# LoRa_Concentrator.net
KiCad netlist of a schematic drawn in Altium Designer
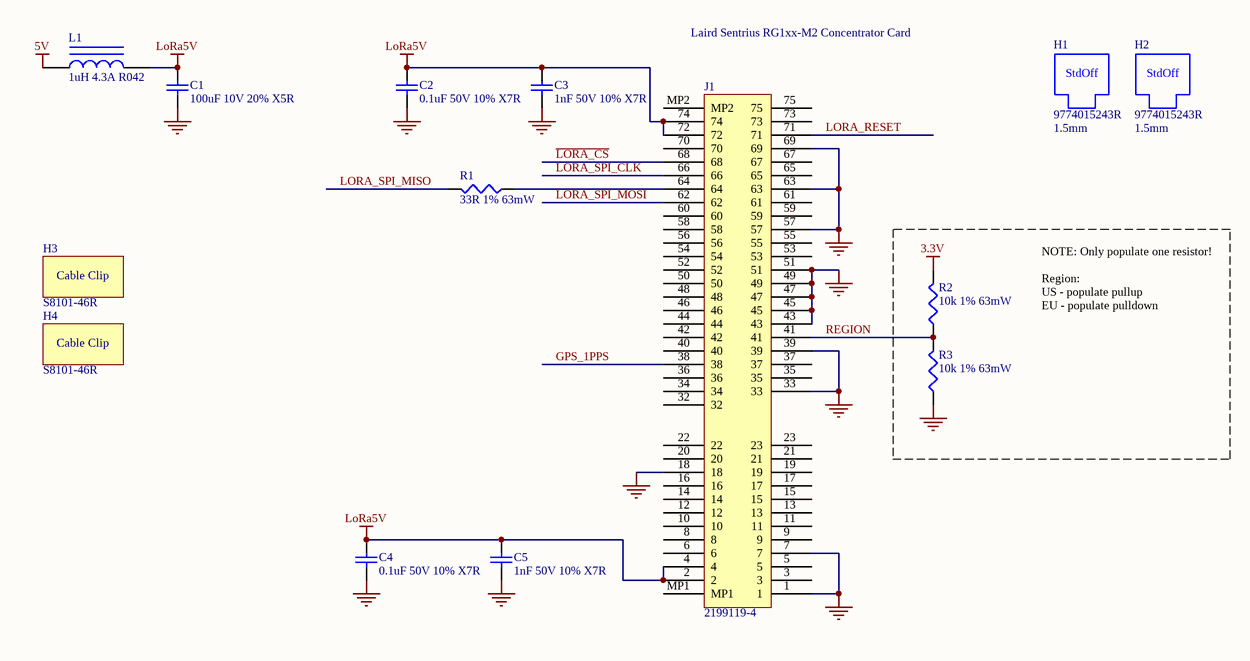
[diagram p0: LoRa Concentrator.SchDoc]

(export (version "E")
  (design (tool "Eeschema 10.0.6"))
  (components
    (comp (ref "C1")
      (value "100uF 10V 20% X5R")
      (footprint "C1210_L")
      (description "Capacitor")
      (libsource (lib "Miscellaneous Devices") (part "Cap"))
    )
    (comp (ref "C2")
      (value "0.1uF 50V 10% X7R")
      (footprint "CAPC1005L")
      (description "Capacitor")
      (libsource (lib "Miscellaneous Devices") (part "Cap"))
    )
    (comp (ref "C3")
      (value "1nF 50V 10% X7R")
      (footprint "CAPC1005L")
      (description "Capacitor")
      (libsource (lib "Miscellaneous Devices") (part "Cap"))
    )
    (comp (ref "C4")
      (value "0.1uF 50V 10% X7R")
      (footprint "CAPC1005L")
      (description "Capacitor")
      (libsource (lib "Miscellaneous Devices") (part "Cap"))
    )
    (comp (ref "C5")
      (value "1nF 50V 10% X7R")
      (footprint "CAPC1005L")
      (description "Capacitor")
      (libsource (lib "Miscellaneous Devices") (part "Cap"))
    )
    (comp (ref "H1")
      (value "9774015243R")
      (footprint "Wurth 9774015243R")
      (description "RND STANDOFF M2X0.4 STEEL")
      (fields (field (name "MANUFACTURER") "Wurth Electronics Inc") (field (name "HEIGHT") "1.5mm"))
      (libsource (lib "Latium Component Library") (part "SMD 1.5mm Spacer"))
    )
    (comp (ref "H2")
      (value "9774015243R")
      (footprint "Wurth 9774015243R")
      (description "RND STANDOFF M2X0.4 STEEL")
      (fields (field (name "MANUFACTURER") "Wurth Electronics Inc") (field (name "HEIGHT") "1.5mm"))
      (libsource (lib "Latium Component Library") (part "SMD 1.5mm Spacer"))
    )
    (comp (ref "H3")
      (value "S8101-46R")
      (footprint "Coax Cable Clip")
      (description "CBL CLIP C-TYPE SILVER SOLDER")
      (fields (field (name "MANUFACTURER") "Harwin Inc"))
      (libsource (lib "Latium Component Library") (part "Cable Clip"))
    )
    (comp (ref "H4")
      (value "S8101-46R")
      (footprint "Coax Cable Clip")
      (description "CBL CLIP C-TYPE SILVER SOLDER")
      (fields (field (name "MANUFACTURER") "Harwin Inc"))
      (libsource (lib "Latium Component Library") (part "Cable Clip"))
    )
    (comp (ref "J1")
      (value "2199119-4")
      (footprint "TE 2199119-4")
      (description "CONN FEMALE 67POS 0.020 GOLD")
      (fields (field (name "MANUFACTURER") "TE Connectivity AMP Connectors"))
      (libsource (lib "Latium Component Library") (part "TE2199119-4"))
    )
    (comp (ref "L1")
      (value "1uH 4.3A R042")
      (footprint "WE-LQS 252012")
      (description "FIXED IND 1UH 4.3A 42 MOHM SMD")
      (fields
        (field (name "MANUFACTURER PART NUMBER") "DFE252012P-1R0M=P2")
        (field (name "MANUFACTURER") "Murata Electronics")
      )
      (libsource (lib "Miscellaneous Devices") (part "Inductor Iron"))
    )
    (comp (ref "R1")
      (value "33R 1% 63mW")
      (footprint "RESC1005L")
      (description "Resistor")
      (libsource (lib "Miscellaneous Devices") (part "Res3"))
    )
    (comp (ref "R2")
      (value "10k 1% 63mW")
      (footprint "RESC1005L")
      (description "Resistor")
      (libsource (lib "Miscellaneous Devices") (part "Res3"))
    )
    (comp (ref "R3")
      (value "10k 1% 63mW")
      (footprint "RESC1005L")
      (description "Resistor")
      (libsource (lib "Miscellaneous Devices") (part "Res3"))
    )
  )
  (nets
    (net (code "1") (name "/GPS_1PPS") (class "Default")
      (node (ref "J1") (pin "38") (pinfunction "38_38") (pintype "passive"))
    )
    (net (code "2") (name "/LORA_RESET") (class "Default")
      (node (ref "J1") (pin "71") (pinfunction "71_71") (pintype "passive"))
    )
    (net (code "3") (name "/LORA_SPI_CLK") (class "Default")
      (node (ref "J1") (pin "66") (pinfunction "66_66") (pintype "passive"))
    )
    (net (code "4") (name "/LORA_SPI_MISO") (class "Default")
      (node (ref "R1") (pin "2") (pinfunction "2_2") (pintype "passive"))
    )
    (net (code "5") (name "/LORA_SPI_MOSI") (class "Default")
      (node (ref "J1") (pin "62") (pinfunction "62_62") (pintype "passive"))
    )
    (net (code "6") (name "/REGION") (class "Default")
      (node (ref "J1") (pin "41") (pinfunction "41_41") (pintype "passive"))
      (node (ref "R2") (pin "1") (pinfunction "1_1") (pintype "passive"))
      (node (ref "R3") (pin "2") (pinfunction "2_2") (pintype "passive"))
    )
    (net (code "7") (name "/~{LORA_CS}") (class "Default")
      (node (ref "J1") (pin "68") (pinfunction "68_68") (pintype "passive"))
    )
    (net (code "8") (name "3.3V") (class "Default")
      (node (ref "R2") (pin "2") (pinfunction "2_2") (pintype "passive"))
    )
    (net (code "9") (name "5V") (class "Default")
      (node (ref "L1") (pin "1") (pinfunction "1_1") (pintype "passive"))
    )
    (net (code "10") (name "GND") (class "Default")
      (node (ref "C1") (pin "1") (pinfunction "1_1") (pintype "passive"))
      (node (ref "C2") (pin "2") (pinfunction "2_2") (pintype "passive"))
      (node (ref "C3") (pin "2") (pinfunction "2_2") (pintype "passive"))
      (node (ref "C4") (pin "2") (pinfunction "2_2") (pintype "passive"))
      (node (ref "C5") (pin "2") (pinfunction "2_2") (pintype "passive"))
      (node (ref "J1") (pin "1") (pinfunction "1_1") (pintype "passive"))
      (node (ref "J1") (pin "18") (pinfunction "18_18") (pintype "passive"))
      (node (ref "J1") (pin "33") (pinfunction "33_33") (pintype "passive"))
      (node (ref "J1") (pin "39") (pinfunction "39_39") (pintype "passive"))
      (node (ref "J1") (pin "43") (pinfunction "43_43") (pintype "passive"))
      (node (ref "J1") (pin "45") (pinfunction "45_45") (pintype "passive"))
      (node (ref "J1") (pin "47") (pinfunction "47_47") (pintype "passive"))
      (node (ref "J1") (pin "49") (pinfunction "49_49") (pintype "passive"))
      (node (ref "J1") (pin "51") (pinfunction "51_51") (pintype "passive"))
      (node (ref "J1") (pin "57") (pinfunction "57_57") (pintype "passive"))
      (node (ref "J1") (pin "63") (pinfunction "63_63") (pintype "passive"))
      (node (ref "J1") (pin "69") (pinfunction "69_69") (pintype "passive"))
      (node (ref "J1") (pin "7") (pinfunction "7_7") (pintype "passive"))
      (node (ref "R3") (pin "1") (pinfunction "1_1") (pintype "passive"))
    )
    (net (code "11") (name "LoRa5V") (class "Default")
      (node (ref "C1") (pin "2") (pinfunction "2_2") (pintype "passive"))
      (node (ref "C2") (pin "1") (pinfunction "1_1") (pintype "passive"))
      (node (ref "C3") (pin "1") (pinfunction "1_1") (pintype "passive"))
      (node (ref "C4") (pin "1") (pinfunction "1_1") (pintype "passive"))
      (node (ref "C5") (pin "1") (pinfunction "1_1") (pintype "passive"))
      (node (ref "J1") (pin "2") (pinfunction "2_2") (pintype "passive"))
      (node (ref "J1") (pin "4") (pinfunction "4_4") (pintype "passive"))
      (node (ref "J1") (pin "72") (pinfunction "72_72") (pintype "passive"))
      (node (ref "J1") (pin "74") (pinfunction "74_74") (pintype "passive"))
      (node (ref "L1") (pin "2") (pinfunction "2_2") (pintype "passive"))
    )
    (net (code "12") (name "Net-(J1-Pad64)") (class "Default")
      (node (ref "J1") (pin "64") (pinfunction "64_64") (pintype "passive"))
      (node (ref "R1") (pin "1") (pinfunction "1_1") (pintype "passive"))
    )
    (net (code "13") (name "unconnected-(J1-Pad3)") (class "Default")
      (node (ref "J1") (pin "3") (pinfunction "3_3") (pintype "passive"))
    )
    (net (code "14") (name "unconnected-(J1-Pad5)") (class "Default")
      (node (ref "J1") (pin "5") (pinfunction "5_5") (pintype "passive"))
    )
    (net (code "15") (name "unconnected-(J1-Pad6)") (class "Default")
      (node (ref "J1") (pin "6") (pinfunction "6_6") (pintype "passive"))
    )
    (net (code "16") (name "unconnected-(J1-Pad8)") (class "Default")
      (node (ref "J1") (pin "8") (pinfunction "8_8") (pintype "passive"))
    )
    (net (code "17") (name "unconnected-(J1-Pad9)") (class "Default")
      (node (ref "J1") (pin "9") (pinfunction "9_9") (pintype "passive"))
    )
    (net (code "18") (name "unconnected-(J1-Pad10)") (class "Default")
      (node (ref "J1") (pin "10") (pinfunction "10_10") (pintype "passive"))
    )
    (net (code "19") (name "unconnected-(J1-Pad11)") (class "Default")
      (node (ref "J1") (pin "11") (pinfunction "11_11") (pintype "passive"))
    )
    (net (code "20") (name "unconnected-(J1-Pad12)") (class "Default")
      (node (ref "J1") (pin "12") (pinfunction "12_12") (pintype "passive"))
    )
    (net (code "21") (name "unconnected-(J1-Pad13)") (class "Default")
      (node (ref "J1") (pin "13") (pinfunction "13_13") (pintype "passive"))
    )
    (net (code "22") (name "unconnected-(J1-Pad14)") (class "Default")
      (node (ref "J1") (pin "14") (pinfunction "14_14") (pintype "passive"))
    )
    (net (code "23") (name "unconnected-(J1-Pad15)") (class "Default")
      (node (ref "J1") (pin "15") (pinfunction "15_15") (pintype "passive"))
    )
    (net (code "24") (name "unconnected-(J1-Pad16)") (class "Default")
      (node (ref "J1") (pin "16") (pinfunction "16_16") (pintype "passive"))
    )
    (net (code "25") (name "unconnected-(J1-Pad17)") (class "Default")
      (node (ref "J1") (pin "17") (pinfunction "17_17") (pintype "passive"))
    )
    (net (code "26") (name "unconnected-(J1-Pad19)") (class "Default")
      (node (ref "J1") (pin "19") (pinfunction "19_19") (pintype "passive"))
    )
    (net (code "27") (name "unconnected-(J1-Pad20)") (class "Default")
      (node (ref "J1") (pin "20") (pinfunction "20_20") (pintype "passive"))
    )
    (net (code "28") (name "unconnected-(J1-Pad21)") (class "Default")
      (node (ref "J1") (pin "21") (pinfunction "21_21") (pintype "passive"))
    )
    (net (code "29") (name "unconnected-(J1-Pad22)") (class "Default")
      (node (ref "J1") (pin "22") (pinfunction "22_22") (pintype "passive"))
    )
    (net (code "30") (name "unconnected-(J1-Pad23)") (class "Default")
      (node (ref "J1") (pin "23") (pinfunction "23_23") (pintype "passive"))
    )
    (net (code "31") (name "unconnected-(J1-Pad32)") (class "Default")
      (node (ref "J1") (pin "32") (pinfunction "32_32") (pintype "passive"))
    )
    (net (code "32") (name "unconnected-(J1-Pad34)") (class "Default")
      (node (ref "J1") (pin "34") (pinfunction "34_34") (pintype "passive"))
    )
    (net (code "33") (name "unconnected-(J1-Pad35)") (class "Default")
      (node (ref "J1") (pin "35") (pinfunction "35_35") (pintype "passive"))
    )
    (net (code "34") (name "unconnected-(J1-Pad36)") (class "Default")
      (node (ref "J1") (pin "36") (pinfunction "36_36") (pintype "passive"))
    )
    (net (code "35") (name "unconnected-(J1-Pad37)") (class "Default")
      (node (ref "J1") (pin "37") (pinfunction "37_37") (pintype "passive"))
    )
    (net (code "36") (name "unconnected-(J1-Pad40)") (class "Default")
      (node (ref "J1") (pin "40") (pinfunction "40_40") (pintype "passive"))
    )
    (net (code "37") (name "unconnected-(J1-Pad42)") (class "Default")
      (node (ref "J1") (pin "42") (pinfunction "42_42") (pintype "passive"))
    )
    (net (code "38") (name "unconnected-(J1-Pad44)") (class "Default")
      (node (ref "J1") (pin "44") (pinfunction "44_44") (pintype "passive"))
    )
    (net (code "39") (name "unconnected-(J1-Pad46)") (class "Default")
      (node (ref "J1") (pin "46") (pinfunction "46_46") (pintype "passive"))
    )
    (net (code "40") (name "unconnected-(J1-Pad48)") (class "Default")
      (node (ref "J1") (pin "48") (pinfunction "48_48") (pintype "passive"))
    )
    (net (code "41") (name "unconnected-(J1-Pad50)") (class "Default")
      (node (ref "J1") (pin "50") (pinfunction "50_50") (pintype "passive"))
    )
    (net (code "42") (name "unconnected-(J1-Pad52)") (class "Default")
      (node (ref "J1") (pin "52") (pinfunction "52_52") (pintype "passive"))
    )
    (net (code "43") (name "unconnected-(J1-Pad53)") (class "Default")
      (node (ref "J1") (pin "53") (pinfunction "53_53") (pintype "passive"))
    )
    (net (code "44") (name "unconnected-(J1-Pad54)") (class "Default")
      (node (ref "J1") (pin "54") (pinfunction "54_54") (pintype "passive"))
    )
    (net (code "45") (name "unconnected-(J1-Pad55)") (class "Default")
      (node (ref "J1") (pin "55") (pinfunction "55_55") (pintype "passive"))
    )
    (net (code "46") (name "unconnected-(J1-Pad56)") (class "Default")
      (node (ref "J1") (pin "56") (pinfunction "56_56") (pintype "passive"))
    )
    (net (code "47") (name "unconnected-(J1-Pad58)") (class "Default")
      (node (ref "J1") (pin "58") (pinfunction "58_58") (pintype "passive"))
    )
    (net (code "48") (name "unconnected-(J1-Pad59)") (class "Default")
      (node (ref "J1") (pin "59") (pinfunction "59_59") (pintype "passive"))
    )
    (net (code "49") (name "unconnected-(J1-Pad60)") (class "Default")
      (node (ref "J1") (pin "60") (pinfunction "60_60") (pintype "passive"))
    )
    (net (code "50") (name "unconnected-(J1-Pad61)") (class "Default")
      (node (ref "J1") (pin "61") (pinfunction "61_61") (pintype "passive"))
    )
    (net (code "51") (name "unconnected-(J1-Pad65)") (class "Default")
      (node (ref "J1") (pin "65") (pinfunction "65_65") (pintype "passive"))
    )
    (net (code "52") (name "unconnected-(J1-Pad67)") (class "Default")
      (node (ref "J1") (pin "67") (pinfunction "67_67") (pintype "passive"))
    )
    (net (code "53") (name "unconnected-(J1-Pad70)") (class "Default")
      (node (ref "J1") (pin "70") (pinfunction "70_70") (pintype "passive"))
    )
    (net (code "54") (name "unconnected-(J1-Pad73)") (class "Default")
      (node (ref "J1") (pin "73") (pinfunction "73_73") (pintype "passive"))
    )
    (net (code "55") (name "unconnected-(J1-Pad75)") (class "Default")
      (node (ref "J1") (pin "75") (pinfunction "75_75") (pintype "passive"))
    )
    (net (code "56") (name "unconnected-(J1-PadMP1)") (class "Default")
      (node (ref "J1") (pin "MP1") (pinfunction "MP1_MP1") (pintype "passive"))
    )
    (net (code "57") (name "unconnected-(J1-PadMP2)") (class "Default")
      (node (ref "J1") (pin "MP2") (pinfunction "MP2_MP2") (pintype "passive"))
    )
  )
)
